# ui_conn.net
KiCad netlist of a schematic drawn in Altium Designer
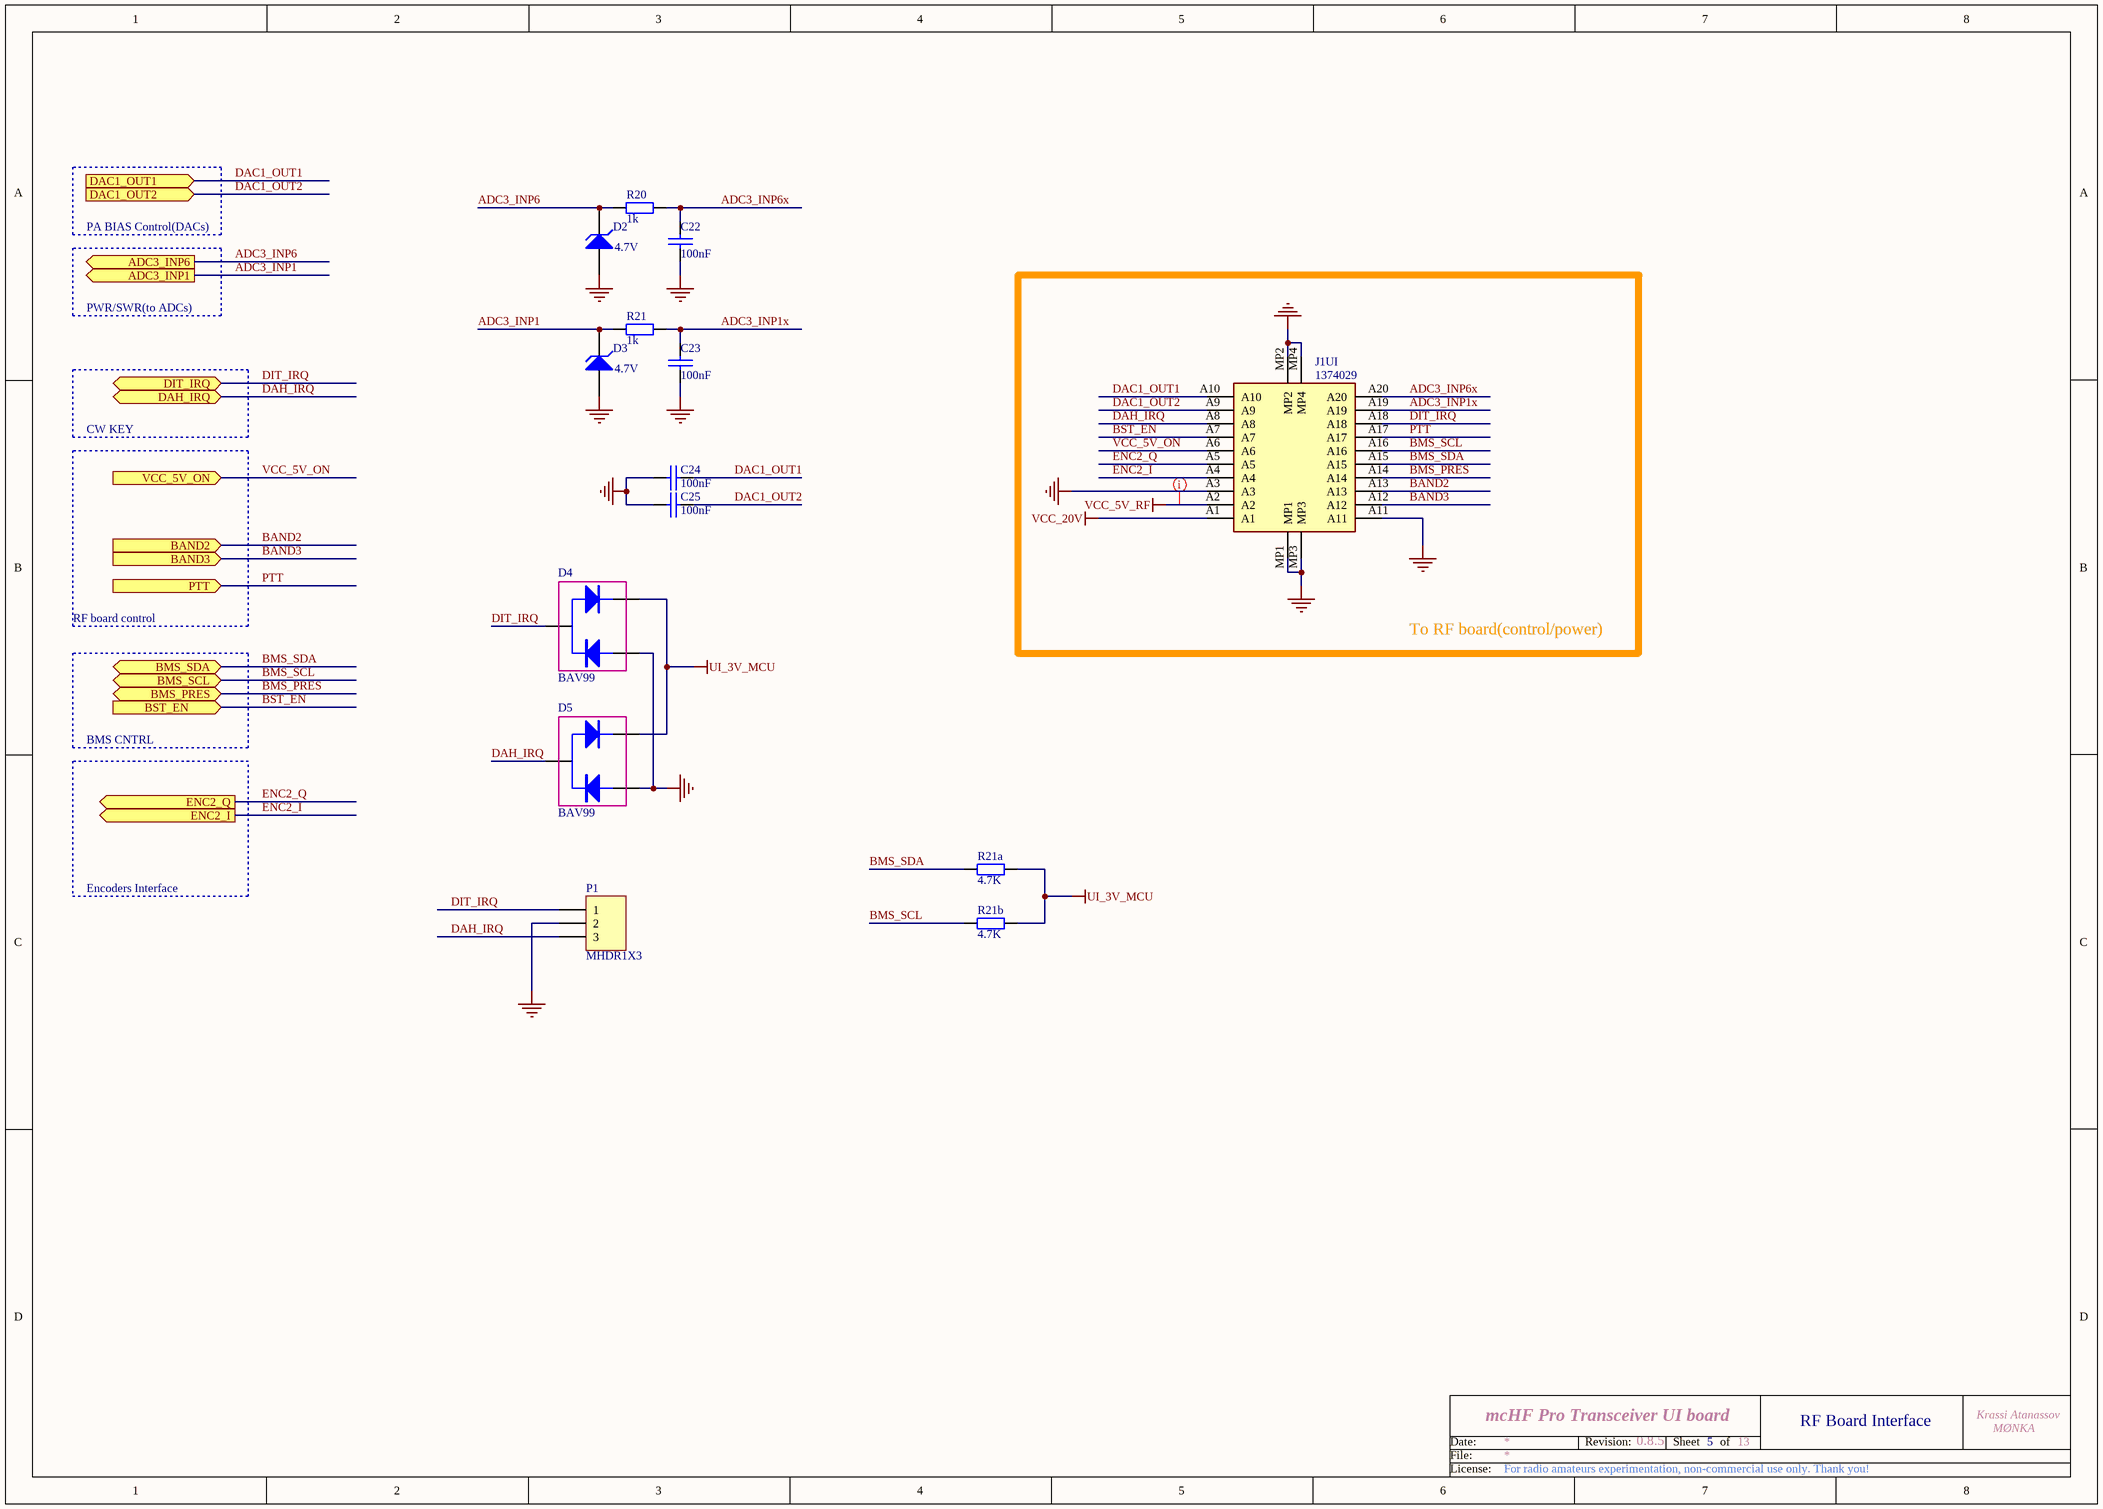
[diagram p0: ui_conn.SchDoc]

(export (version "E")
  (design (tool "Eeschema 10.0.6"))
  (components
    (comp (ref "C22")
      (value "100nF")
      (footprint "0805")
      (description "Capacitor")
      (libsource (lib "mcHF_ui") (part "CAP"))
    )
    (comp (ref "C23")
      (value "100nF")
      (footprint "0805")
      (description "Capacitor")
      (libsource (lib "mcHF_ui") (part "CAP"))
    )
    (comp (ref "C24")
      (value "100nF")
      (footprint "0805")
      (description "Capacitor")
      (libsource (lib "mcHF_ui") (part "CAP"))
    )
    (comp (ref "C25")
      (value "100nF")
      (footprint "0805")
      (description "Capacitor")
      (libsource (lib "mcHF_ui") (part "CAP"))
    )
    (comp (ref "D2")
      (value "4.7V")
      (footprint "0805P")
      (description "Zener Diode")
      (fields (field (name "PUBLISHER") "Altium Limited"))
      (libsource (lib "Miscellaneous Devices") (part "D Zener"))
    )
    (comp (ref "D3")
      (value "4.7V")
      (footprint "0805P")
      (description "Zener Diode")
      (fields (field (name "PUBLISHER") "Altium Limited"))
      (libsource (lib "Miscellaneous Devices") (part "D Zener"))
    )
    (comp (ref "D4")
      (value "BAV99")
      (footprint "SOT-23")
      (description "Small Signal Diode, Dual Series")
      (libsource (lib "mcHF_rf") (part "BAV99"))
    )
    (comp (ref "D5")
      (value "BAV99")
      (footprint "SOT-23")
      (description "Small Signal Diode, Dual Series")
      (libsource (lib "mcHF_rf") (part "BAV99"))
    )
    (comp (ref "J1UI")
      (value "1374029")
      (footprint "1373866")
      (fields
        (field (name "MOUSER PART NUMBER") "651-1373866")
        (field (name "MANUFACTURER_PART_NUMBER") "1373866")
      )
      (libsource (lib "1373866") (part "1373866"))
    )
    (comp (ref "P1")
      (value "MHDR1X3")
      (footprint "MHDR1X3")
      (description "Header, 3-Pin")
      (fields (field (name "PUBLISHER") "Altium Limited"))
      (libsource (lib "Miscellaneous Connectors") (part "MHDR1X3"))
    )
    (comp (ref "R20")
      (value "1k")
      (footprint "0805")
      (description "Resistor")
      (libsource (lib "mcHF_ui") (part "RES"))
    )
    (comp (ref "R21")
      (value "1k")
      (footprint "0805")
      (description "Resistor")
      (libsource (lib "mcHF_ui") (part "RES"))
    )
    (comp (ref "R21a")
      (value "4.7K")
      (footprint "0805")
      (description "Resistor")
      (libsource (lib "*") (part "RES"))
    )
    (comp (ref "R21b")
      (value "4.7K")
      (footprint "0805")
      (description "Resistor")
      (libsource (lib "*") (part "RES"))
    )
  )
  (nets
    (net (code "1") (name "/ADC3_INP1") (class "Default")
      (node (ref "D3") (pin "2") (pinfunction "K_2") (pintype "passive"))
      (node (ref "R21") (pin "2") (pinfunction "2_2") (pintype "passive"))
    )
    (net (code "2") (name "/ADC3_INP1x") (class "Default")
      (node (ref "C23") (pin "2") (pinfunction "2_2") (pintype "passive"))
      (node (ref "J1UI") (pin "A19") (pinfunction "A19_A19") (pintype "passive"))
      (node (ref "R21") (pin "1") (pinfunction "1_1") (pintype "passive"))
    )
    (net (code "3") (name "/ADC3_INP6") (class "Default")
      (node (ref "D2") (pin "2") (pinfunction "K_2") (pintype "passive"))
      (node (ref "R20") (pin "2") (pinfunction "2_2") (pintype "passive"))
    )
    (net (code "4") (name "/ADC3_INP6x") (class "Default")
      (node (ref "C22") (pin "2") (pinfunction "2_2") (pintype "passive"))
      (node (ref "J1UI") (pin "A20") (pinfunction "A20_A20") (pintype "passive"))
      (node (ref "R20") (pin "1") (pinfunction "1_1") (pintype "passive"))
    )
    (net (code "5") (name "/BAND2") (class "Default")
      (node (ref "J1UI") (pin "A13") (pinfunction "A13_A13") (pintype "passive"))
    )
    (net (code "6") (name "/BAND3") (class "Default")
      (node (ref "J1UI") (pin "A12") (pinfunction "A12_A12") (pintype "passive"))
    )
    (net (code "7") (name "/BMS_PRES") (class "Default")
      (node (ref "J1UI") (pin "A14") (pinfunction "A14_A14") (pintype "passive"))
    )
    (net (code "8") (name "/BMS_SCL") (class "Default")
      (node (ref "J1UI") (pin "A16") (pinfunction "A16_A16") (pintype "passive"))
      (node (ref "R21b") (pin "1") (pinfunction "1_1") (pintype "passive"))
    )
    (net (code "9") (name "/BMS_SDA") (class "Default")
      (node (ref "J1UI") (pin "A15") (pinfunction "A15_A15") (pintype "passive"))
      (node (ref "R21a") (pin "1") (pinfunction "1_1") (pintype "passive"))
    )
    (net (code "10") (name "/BST_EN") (class "Default")
      (node (ref "J1UI") (pin "A7") (pinfunction "A7_A7") (pintype "passive"))
    )
    (net (code "11") (name "/DAC1_OUT1") (class "Default")
      (node (ref "C24") (pin "1") (pinfunction "1_1") (pintype "passive"))
      (node (ref "J1UI") (pin "A10") (pinfunction "A10_A10") (pintype "passive"))
    )
    (net (code "12") (name "/DAC1_OUT2") (class "Default")
      (node (ref "C25") (pin "1") (pinfunction "1_1") (pintype "passive"))
      (node (ref "J1UI") (pin "A9") (pinfunction "A9_A9") (pintype "passive"))
    )
    (net (code "13") (name "/DAH_IRQ") (class "Default")
      (node (ref "D5") (pin "3") (pinfunction "C_3") (pintype "passive"))
      (node (ref "J1UI") (pin "A8") (pinfunction "A8_A8") (pintype "passive"))
      (node (ref "P1") (pin "3") (pinfunction "3_3") (pintype "passive"))
    )
    (net (code "14") (name "/DIT_IRQ") (class "Default")
      (node (ref "D4") (pin "3") (pinfunction "C_3") (pintype "passive"))
      (node (ref "J1UI") (pin "A18") (pinfunction "A18_A18") (pintype "passive"))
      (node (ref "P1") (pin "1") (pinfunction "1_1") (pintype "passive"))
    )
    (net (code "15") (name "/ENC2_I") (class "Default")
      (node (ref "J1UI") (pin "A4") (pinfunction "A4_A4") (pintype "passive"))
    )
    (net (code "16") (name "/ENC2_Q") (class "Default")
      (node (ref "J1UI") (pin "A5") (pinfunction "A5_A5") (pintype "passive"))
    )
    (net (code "17") (name "/PTT") (class "Default")
      (node (ref "J1UI") (pin "A17") (pinfunction "A17_A17") (pintype "passive"))
    )
    (net (code "18") (name "/VCC_5V_ON") (class "Default")
      (node (ref "J1UI") (pin "A6") (pinfunction "A6_A6") (pintype "passive"))
    )
    (net (code "19") (name "GND") (class "Default")
      (node (ref "C22") (pin "1") (pinfunction "1_1") (pintype "passive"))
      (node (ref "C23") (pin "1") (pinfunction "1_1") (pintype "passive"))
      (node (ref "C24") (pin "2") (pinfunction "2_2") (pintype "passive"))
      (node (ref "C25") (pin "2") (pinfunction "2_2") (pintype "passive"))
      (node (ref "D2") (pin "1") (pinfunction "A_1") (pintype "passive"))
      (node (ref "D3") (pin "1") (pinfunction "A_1") (pintype "passive"))
      (node (ref "D4") (pin "1") (pinfunction "A1_1") (pintype "passive"))
      (node (ref "D5") (pin "1") (pinfunction "A1_1") (pintype "passive"))
      (node (ref "J1UI") (pin "A11") (pinfunction "A11_A11") (pintype "passive"))
      (node (ref "J1UI") (pin "A3") (pinfunction "A3_A3") (pintype "passive"))
      (node (ref "J1UI") (pin "MP1") (pinfunction "MP1_MP1") (pintype "passive"))
      (node (ref "J1UI") (pin "MP2") (pinfunction "MP2_MP2") (pintype "passive"))
      (node (ref "J1UI") (pin "MP3") (pinfunction "MP3_MP3") (pintype "passive"))
      (node (ref "J1UI") (pin "MP4") (pinfunction "MP4_MP4") (pintype "passive"))
      (node (ref "P1") (pin "2") (pinfunction "2_2") (pintype "passive"))
    )
    (net (code "20") (name "UI_3V_MCU") (class "Default")
      (node (ref "D4") (pin "2") (pinfunction "K1_2") (pintype "passive"))
      (node (ref "D5") (pin "2") (pinfunction "K1_2") (pintype "passive"))
      (node (ref "R21a") (pin "2") (pinfunction "2_2") (pintype "passive"))
      (node (ref "R21b") (pin "2") (pinfunction "2_2") (pintype "passive"))
    )
    (net (code "21") (name "VCC_5V_RF") (class "Default")
      (node (ref "J1UI") (pin "A2") (pinfunction "A2_A2") (pintype "passive"))
    )
    (net (code "22") (name "VCC_20V") (class "Default")
      (node (ref "J1UI") (pin "A1") (pinfunction "A1_A1") (pintype "passive"))
    )
  )
)
